# SIM7600G-H.net
KiCad netlist of a schematic drawn in Altium Designer
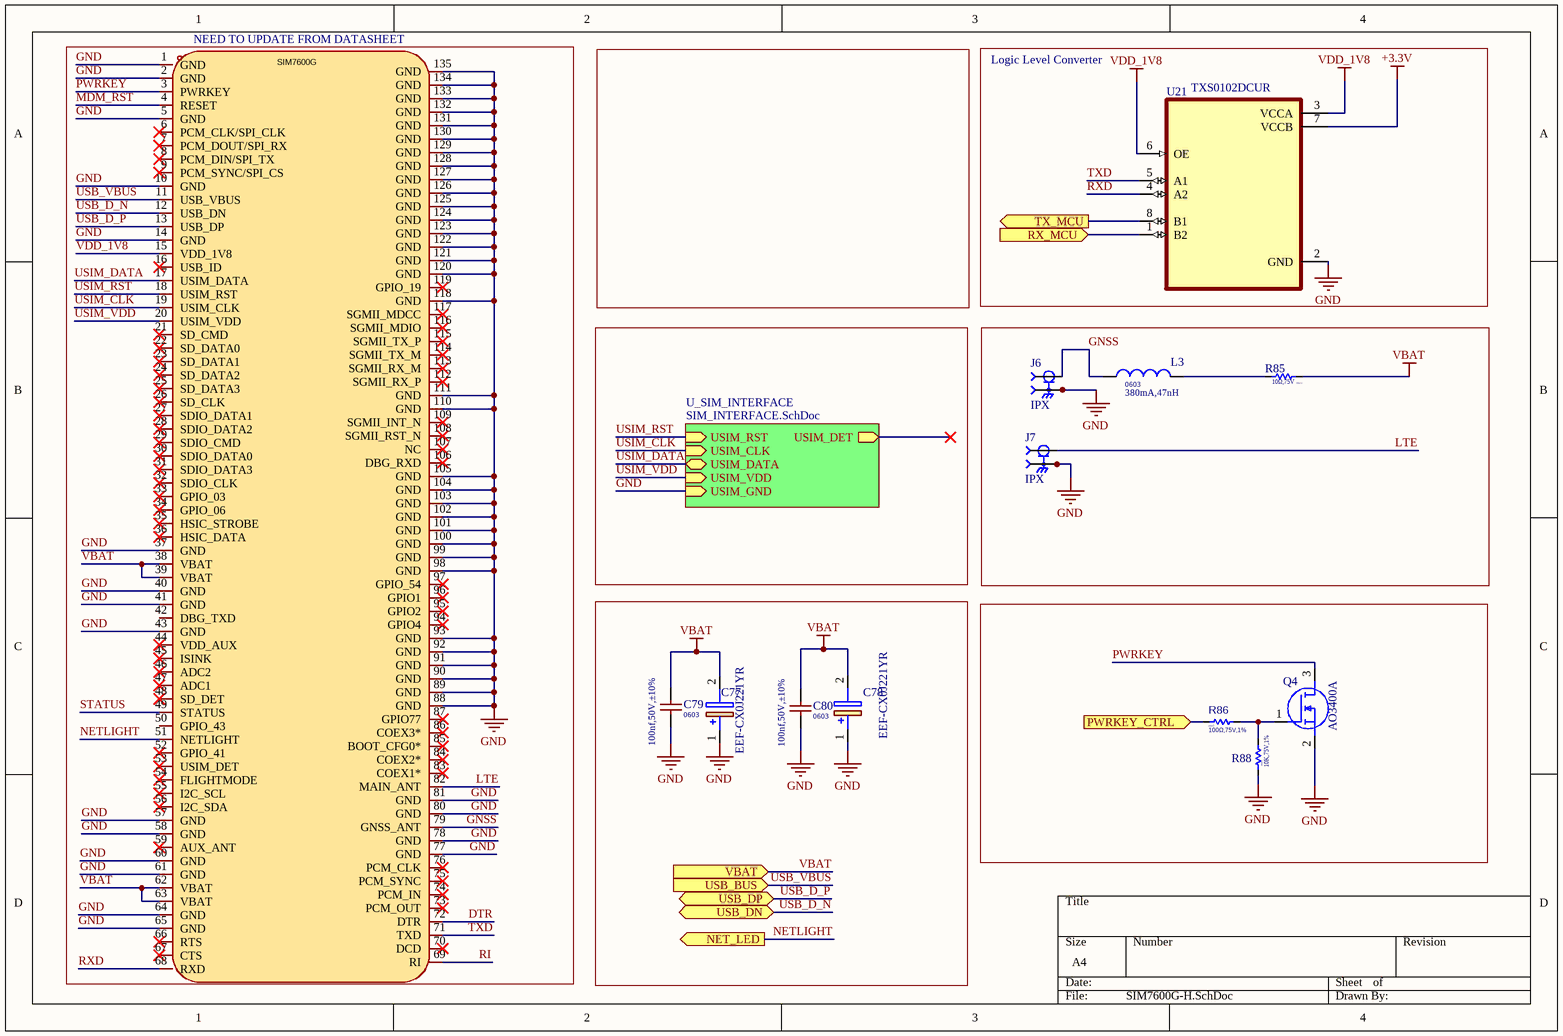
[diagram p0: SIM7600G-H.SchDoc]

(export (version "E")
  (design (tool "Eeschema 10.0.6"))
  (components
    (comp (ref "C77")
      (value "EEF-CX0J221YR")
      (footprint "CAPPM7343X200N")
      (description "Capacitor Polarised")
      (libsource (lib "RCL") (part "EEF-CX0J221YR"))
    )
    (comp (ref "C78")
      (value "EEF-CX0J221YR")
      (footprint "CAPPM7343X200N")
      (description "Capacitor Polarised")
      (libsource (lib "RCL") (part "EEF-CX0J221YR"))
    )
    (comp (ref "C79")
      (value "100nf,50V,±10%")
      (footprint "C0603")
      (description "50V 100nF X7R ±10% 0603 Multilayer Ceramic Capacitors MLCC - SMD/SMT ROHS")
      (fields
        (field (name "MPN") "603-CC603KRX7R9BB104")
        (field (name "MANUFACTURER") "KEMET")
        (field (name "PACKAGE") "0603")
      )
      (libsource (lib "RCL") (part "CC0603KRX7R9BB104"))
    )
    (comp (ref "C80")
      (value "100nf,50V,±10%")
      (footprint "C0603")
      (description "50V 100nF X7R ±10% 0603 Multilayer Ceramic Capacitors MLCC - SMD/SMT ROHS")
      (fields
        (field (name "MPN") "603-CC603KRX7R9BB104")
        (field (name "MANUFACTURER") "KEMET")
        (field (name "PACKAGE") "0603")
      )
      (libsource (lib "RCL") (part "CC0603KRX7R9BB104"))
    )
    (comp (ref "J6")
      (value "IPX")
      (footprint "connector_button:IPEX_20279-001E-03")
      (description "Small form factor with big performance through 6 GHz")
      (fields (field (name "MANUFACTURER") "I-PEX") (field (name "MPN") "20279-001E-03"))
      (libsource (lib "connector_button") (part "20279-001E-03"))
    )
    (comp (ref "J7")
      (value "IPX")
      (footprint "connector_button:IPEX_20279-001E-03")
      (description "Small form factor with big performance through 6 GHz")
      (fields (field (name "MANUFACTURER") "I-PEX") (field (name "MPN") "20279-001E-03"))
      (libsource (lib "connector_button") (part "20279-001E-03"))
    )
    (comp (ref "L3")
      (value "380mA,47nH")
      (footprint "LQW18AN47NG00D")
      (description "47 nH Unshielded Drum Core, Wirewound Inductor 380 mA 290mOhm Max 0603 (1608 Metric)")
      (fields
        (field (name "MPN") "LQW18AN47NG00D")
        (field (name "MANUFACTURER") "Murata Electronics")
        (field (name "PACKAGE") "0603")
      )
      (libsource (lib "RCL") (part "LQW18AN47NG00D"))
    )
    (comp (ref "Q4")
      (value "AO3400A")
      (footprint "SOT95P280X125-3N")
      (description "MOSFET (N-Channel)")
      (libsource (lib "MOS_TRAN") (part "AO3400A"))
    )
    (comp (ref "R85")
      (value "10Ω,75V")
      (footprint "R0603")
      (fields
        (field (name "MANUFACTURER") "Ever Ohms Tech")
        (field (name "MPN") "QR0603J10R0P05Z")
        (field (name "PACKAGE") "0603")
        (field (name "Comment") "10R")
      )
      (libsource (lib "RCL") (part "QR0603J10R0P05Z"))
    )
    (comp (ref "R86")
      (value "100Ω,75V,1%")
      (footprint "R0603")
      (description "100mW Thick Film Resistors 75V ±100ppm/℃ ±1% 100Ω 0603 Chip Resistor - Surface Mount ROHS")
      (fields
        (field (name "MANUFACTURER") "YAGEO(国巨)")
        (field (name "MPN") "AC0603FR-13100RL")
        (field (name "PACKAGE") "0603")
      )
      (libsource (lib "RCL") (part "AC0603FR-13100RL"))
    )
    (comp (ref "R88")
      (value "10K,75V,1%")
      (footprint "R0603")
      (description "100mW Thick Film Resistors ±100ppm/℃ ±1% 10kΩ 0603 Chip Resistor - Surface Mount ROHS")
      (fields
        (field (name "MPN") "0603WAF1002T5E")
        (field (name "MANUFACTURER") "UNI-ROYAL(Uniroyal Elec)")
        (field (name "PACKAGE") "0603")
      )
      (libsource (lib "RCL") (part "0603WAF1002T5E"))
    )
    (comp (ref "U21")
      (value "TXS0102DCUR")
      (footprint "IC:8-VSSOP")
      (fields (field (name "MANUFACTURER") "Texas Instruments"))
      (libsource (lib "IC") (part "TXS0102DCUR"))
    )
    (comp (ref "U22")
      (value "SIM7600G")
      (footprint "SMD,30x30mm")
      (description "SMD,30x30mm 2G/3G/4G/5G Modules ROHS")
      (fields (field (name "MANUFACTURER") "SIMCOM"))
      (libsource (lib "Module") (part "SIM7600G"))
    )
  )
  (nets
    (net (code "1") (name "+3.3V") (class "Default")
      (node (ref "U21") (pin "7") (pinfunction "VCCB_7") (pintype "power_in"))
    )
    (net (code "2") (name "/DTR") (class "Default")
      (node (ref "U22") (pin "72") (pinfunction "DTR_72") (pintype "passive"))
    )
    (net (code "3") (name "/GNSS") (class "Default")
      (node (ref "J6") (pin "1") (pinfunction "SIG_1") (pintype "passive"))
      (node (ref "L3") (pin "1") (pinfunction "1_1") (pintype "passive"))
      (node (ref "U22") (pin "79") (pinfunction "GNSS_ANT_79") (pintype "passive"))
    )
    (net (code "4") (name "/LTE") (class "Default")
      (node (ref "J7") (pin "1") (pinfunction "SIG_1") (pintype "passive"))
      (node (ref "U22") (pin "82") (pinfunction "MAIN_ANT_82") (pintype "passive"))
    )
    (net (code "5") (name "/MDM_RST") (class "Default")
      (node (ref "U22") (pin "4") (pinfunction "RESET_4") (pintype "passive"))
    )
    (net (code "6") (name "/NETLIGHT") (class "Default")
      (node (ref "U22") (pin "51") (pinfunction "NETLIGHT_51") (pintype "passive"))
    )
    (net (code "7") (name "/PWRKEY") (class "Default")
      (node (ref "Q4") (pin "3") (pinfunction "D_3") (pintype "passive"))
      (node (ref "U22") (pin "3") (pinfunction "PWRKEY_3") (pintype "passive"))
    )
    (net (code "8") (name "/PWRKEY_CTRL") (class "Default")
      (node (ref "R86") (pin "1") (pinfunction "1_1") (pintype "passive"))
    )
    (net (code "9") (name "/RI") (class "Default")
      (node (ref "U22") (pin "69") (pinfunction "RI_69") (pintype "passive"))
    )
    (net (code "10") (name "/RXD") (class "Default")
      (node (ref "U21") (pin "4") (pinfunction "A2_4") (pintype "bidirectional"))
      (node (ref "U22") (pin "68") (pinfunction "RXD_68") (pintype "passive"))
    )
    (net (code "11") (name "/RX_MCU") (class "Default")
      (node (ref "U21") (pin "1") (pinfunction "B2_1") (pintype "bidirectional"))
    )
    (net (code "12") (name "/STATUS") (class "Default")
      (node (ref "U22") (pin "49") (pinfunction "STATUS_49") (pintype "passive"))
    )
    (net (code "13") (name "/TXD") (class "Default")
      (node (ref "U21") (pin "5") (pinfunction "A1_5") (pintype "bidirectional"))
      (node (ref "U22") (pin "71") (pinfunction "TXD_71") (pintype "passive"))
    )
    (net (code "14") (name "/TX_MCU") (class "Default")
      (node (ref "U21") (pin "8") (pinfunction "B1_8") (pintype "bidirectional"))
    )
    (net (code "15") (name "/USB_D_N") (class "Default")
      (node (ref "U22") (pin "12") (pinfunction "USB_DN_12") (pintype "passive"))
    )
    (net (code "16") (name "/USB_D_P") (class "Default")
      (node (ref "U22") (pin "13") (pinfunction "USB_DP_13") (pintype "passive"))
    )
    (net (code "17") (name "/USB_VBUS") (class "Default")
      (node (ref "U22") (pin "11") (pinfunction "USB_VBUS_11") (pintype "passive"))
    )
    (net (code "18") (name "/USIM_CLK") (class "Default")
      (node (ref "U22") (pin "19") (pinfunction "USIM_CLK_19") (pintype "passive"))
    )
    (net (code "19") (name "/USIM_DATA") (class "Default")
      (node (ref "U22") (pin "17") (pinfunction "USIM_DATA_17") (pintype "passive"))
    )
    (net (code "21") (name "/USIM_RST") (class "Default")
      (node (ref "U22") (pin "18") (pinfunction "USIM_RST_18") (pintype "passive"))
    )
    (net (code "22") (name "/USIM_VDD") (class "Default")
      (node (ref "U22") (pin "20") (pinfunction "USIM_VDD_20") (pintype "passive"))
    )
    (net (code "23") (name "GND") (class "Default")
      (node (ref "C77") (pin "1") (pinfunction "+_1") (pintype "passive"))
      (node (ref "C78") (pin "1") (pinfunction "+_1") (pintype "passive"))
      (node (ref "C79") (pin "1") (pinfunction "1_1") (pintype "passive"))
      (node (ref "C80") (pin "1") (pinfunction "1_1") (pintype "passive"))
      (node (ref "J6") (pin "2") (pinfunction "GND_2") (pintype "passive"))
      (node (ref "J6") (pin "3") (pinfunction "GND_3") (pintype "passive"))
      (node (ref "J7") (pin "2") (pinfunction "GND_2") (pintype "passive"))
      (node (ref "J7") (pin "3") (pinfunction "GND_3") (pintype "passive"))
      (node (ref "Q4") (pin "2") (pinfunction "S_2") (pintype "passive"))
      (node (ref "R88") (pin "1") (pinfunction "1_1") (pintype "passive"))
      (node (ref "U21") (pin "2") (pinfunction "GND_2") (pintype "power_in"))
      (node (ref "U22") (pin "1") (pinfunction "GND_1") (pintype "passive"))
      (node (ref "U22") (pin "10") (pinfunction "GND_10") (pintype "passive"))
      (node (ref "U22") (pin "100") (pinfunction "GND_100") (pintype "passive"))
      (node (ref "U22") (pin "101") (pinfunction "GND_101") (pintype "passive"))
      (node (ref "U22") (pin "102") (pinfunction "GND_102") (pintype "passive"))
      (node (ref "U22") (pin "103") (pinfunction "GND_103") (pintype "passive"))
      (node (ref "U22") (pin "104") (pinfunction "GND_104") (pintype "passive"))
      (node (ref "U22") (pin "105") (pinfunction "GND_105") (pintype "passive"))
      (node (ref "U22") (pin "110") (pinfunction "GND_110") (pintype "passive"))
      (node (ref "U22") (pin "111") (pinfunction "GND_111") (pintype "passive"))
      (node (ref "U22") (pin "118") (pinfunction "GND_118") (pintype "passive"))
      (node (ref "U22") (pin "120") (pinfunction "GND_120") (pintype "passive"))
      (node (ref "U22") (pin "121") (pinfunction "GND_121") (pintype "passive"))
      (node (ref "U22") (pin "122") (pinfunction "GND_122") (pintype "passive"))
      (node (ref "U22") (pin "123") (pinfunction "GND_123") (pintype "passive"))
      (node (ref "U22") (pin "124") (pinfunction "GND_124") (pintype "passive"))
      (node (ref "U22") (pin "125") (pinfunction "GND_125") (pintype "passive"))
      (node (ref "U22") (pin "126") (pinfunction "GND_126") (pintype "passive"))
      (node (ref "U22") (pin "127") (pinfunction "GND_127") (pintype "passive"))
      (node (ref "U22") (pin "128") (pinfunction "GND_128") (pintype "passive"))
      (node (ref "U22") (pin "129") (pinfunction "GND_129") (pintype "passive"))
      (node (ref "U22") (pin "130") (pinfunction "GND_130") (pintype "passive"))
      (node (ref "U22") (pin "131") (pinfunction "GND_131") (pintype "passive"))
      (node (ref "U22") (pin "132") (pinfunction "GND_132") (pintype "passive"))
      (node (ref "U22") (pin "133") (pinfunction "GND_133") (pintype "passive"))
      (node (ref "U22") (pin "134") (pinfunction "GND_134") (pintype "passive"))
      (node (ref "U22") (pin "135") (pinfunction "GND_135") (pintype "passive"))
      (node (ref "U22") (pin "14") (pinfunction "GND_14") (pintype "passive"))
      (node (ref "U22") (pin "2") (pinfunction "GND_2") (pintype "passive"))
      (node (ref "U22") (pin "37") (pinfunction "GND_37") (pintype "passive"))
      (node (ref "U22") (pin "40") (pinfunction "GND_40") (pintype "passive"))
      (node (ref "U22") (pin "41") (pinfunction "GND_41") (pintype "passive"))
      (node (ref "U22") (pin "43") (pinfunction "GND_43") (pintype "passive"))
      (node (ref "U22") (pin "5") (pinfunction "GND_5") (pintype "passive"))
      (node (ref "U22") (pin "57") (pinfunction "GND_57") (pintype "passive"))
      (node (ref "U22") (pin "58") (pinfunction "GND_58") (pintype "passive"))
      (node (ref "U22") (pin "60") (pinfunction "GND_60") (pintype "passive"))
      (node (ref "U22") (pin "61") (pinfunction "GND_61") (pintype "passive"))
      (node (ref "U22") (pin "64") (pinfunction "GND_64") (pintype "passive"))
      (node (ref "U22") (pin "65") (pinfunction "GND_65") (pintype "passive"))
      (node (ref "U22") (pin "77") (pinfunction "GND_77") (pintype "passive"))
      (node (ref "U22") (pin "78") (pinfunction "GND_78") (pintype "passive"))
      (node (ref "U22") (pin "80") (pinfunction "GND_80") (pintype "passive"))
      (node (ref "U22") (pin "81") (pinfunction "GND_81") (pintype "passive"))
      (node (ref "U22") (pin "88") (pinfunction "GND_88") (pintype "passive"))
      (node (ref "U22") (pin "89") (pinfunction "GND_89") (pintype "passive"))
      (node (ref "U22") (pin "90") (pinfunction "GND_90") (pintype "passive"))
      (node (ref "U22") (pin "91") (pinfunction "GND_91") (pintype "passive"))
      (node (ref "U22") (pin "92") (pinfunction "GND_92") (pintype "passive"))
      (node (ref "U22") (pin "93") (pinfunction "GND_93") (pintype "passive"))
      (node (ref "U22") (pin "98") (pinfunction "GND_98") (pintype "passive"))
      (node (ref "U22") (pin "99") (pinfunction "GND_99") (pintype "passive"))
    )
    (net (code "24") (name "Net-(L3-Pad2)") (class "Default")
      (node (ref "L3") (pin "2") (pinfunction "2_2") (pintype "passive"))
      (node (ref "R85") (pin "1") (pinfunction "1_1") (pintype "passive"))
    )
    (net (code "25") (name "Net-(Q4-G)") (class "Default")
      (node (ref "Q4") (pin "1") (pinfunction "G_1") (pintype "passive"))
      (node (ref "R86") (pin "2") (pinfunction "2_2") (pintype "passive"))
      (node (ref "R88") (pin "2") (pinfunction "2_2") (pintype "passive"))
    )
    (net (code "26") (name "VBAT") (class "Default")
      (node (ref "C77") (pin "2") (pinfunction "-_2") (pintype "passive"))
      (node (ref "C78") (pin "2") (pinfunction "-_2") (pintype "passive"))
      (node (ref "C79") (pin "2") (pinfunction "2_2") (pintype "passive"))
      (node (ref "C80") (pin "2") (pinfunction "2_2") (pintype "passive"))
      (node (ref "R85") (pin "2") (pinfunction "2_2") (pintype "passive"))
      (node (ref "U22") (pin "38") (pinfunction "VBAT_38") (pintype "passive"))
      (node (ref "U22") (pin "39") (pinfunction "VBAT_39") (pintype "passive"))
      (node (ref "U22") (pin "62") (pinfunction "VBAT_62") (pintype "passive"))
      (node (ref "U22") (pin "63") (pinfunction "VBAT_63") (pintype "passive"))
    )
    (net (code "27") (name "VDD_1V8") (class "Default")
      (node (ref "U21") (pin "3") (pinfunction "VCCA_3") (pintype "power_in"))
      (node (ref "U21") (pin "6") (pinfunction "OE_6") (pintype "input"))
      (node (ref "U22") (pin "15") (pinfunction "VDD_1V8_15") (pintype "passive"))
    )
    (net (code "28") (name "unconnected-(U22-ADC1-Pad47)") (class "Default")
      (node (ref "U22") (pin "47") (pinfunction "ADC1_47") (pintype "passive+no_connect"))
    )
    (net (code "29") (name "unconnected-(U22-ADC2-Pad46)") (class "Default")
      (node (ref "U22") (pin "46") (pinfunction "ADC2_46") (pintype "passive+no_connect"))
    )
    (net (code "30") (name "unconnected-(U22-AUX_ANT-Pad59)") (class "Default")
      (node (ref "U22") (pin "59") (pinfunction "AUX_ANT_59") (pintype "passive+no_connect"))
    )
    (net (code "31") (name "unconnected-(U22-BOOT_CFG0*-Pad85)") (class "Default")
      (node (ref "U22") (pin "85") (pinfunction "BOOT_CFG0*_85") (pintype "passive+no_connect"))
    )
    (net (code "32") (name "unconnected-(U22-COEX1*-Pad83)") (class "Default")
      (node (ref "U22") (pin "83") (pinfunction "COEX1*_83") (pintype "passive+no_connect"))
    )
    (net (code "33") (name "unconnected-(U22-COEX2*-Pad84)") (class "Default")
      (node (ref "U22") (pin "84") (pinfunction "COEX2*_84") (pintype "passive+no_connect"))
    )
    (net (code "34") (name "unconnected-(U22-COEX3*-Pad86)") (class "Default")
      (node (ref "U22") (pin "86") (pinfunction "COEX3*_86") (pintype "passive+no_connect"))
    )
    (net (code "35") (name "unconnected-(U22-CTS-Pad67)") (class "Default")
      (node (ref "U22") (pin "67") (pinfunction "CTS_67") (pintype "passive+no_connect"))
    )
    (net (code "36") (name "unconnected-(U22-DBG_RXD-Pad106)") (class "Default")
      (node (ref "U22") (pin "106") (pinfunction "DBG_RXD_106") (pintype "passive+no_connect"))
    )
    (net (code "37") (name "unconnected-(U22-DBG_TXD-Pad42)") (class "Default")
      (node (ref "U22") (pin "42") (pinfunction "DBG_TXD_42") (pintype "passive"))
    )
    (net (code "38") (name "unconnected-(U22-DCD-Pad70)") (class "Default")
      (node (ref "U22") (pin "70") (pinfunction "DCD_70") (pintype "passive+no_connect"))
    )
    (net (code "39") (name "unconnected-(U22-FLIGHTMODE-Pad54)") (class "Default")
      (node (ref "U22") (pin "54") (pinfunction "FLIGHTMODE_54") (pintype "passive+no_connect"))
    )
    (net (code "40") (name "unconnected-(U22-GPIO1-Pad96)") (class "Default")
      (node (ref "U22") (pin "96") (pinfunction "GPIO1_96") (pintype "passive+no_connect"))
    )
    (net (code "41") (name "unconnected-(U22-GPIO2-Pad95)") (class "Default")
      (node (ref "U22") (pin "95") (pinfunction "GPIO2_95") (pintype "passive+no_connect"))
    )
    (net (code "42") (name "unconnected-(U22-GPIO4-Pad94)") (class "Default")
      (node (ref "U22") (pin "94") (pinfunction "GPIO4_94") (pintype "passive+no_connect"))
    )
    (net (code "43") (name "unconnected-(U22-GPIO77-Pad87)") (class "Default")
      (node (ref "U22") (pin "87") (pinfunction "GPIO77_87") (pintype "passive+no_connect"))
    )
    (net (code "44") (name "unconnected-(U22-GPIO_03-Pad33)") (class "Default")
      (node (ref "U22") (pin "33") (pinfunction "GPIO_03_33") (pintype "passive+no_connect"))
    )
    (net (code "45") (name "unconnected-(U22-GPIO_06-Pad34)") (class "Default")
      (node (ref "U22") (pin "34") (pinfunction "GPIO_06_34") (pintype "passive+no_connect"))
    )
    (net (code "46") (name "unconnected-(U22-GPIO_19-Pad119)") (class "Default")
      (node (ref "U22") (pin "119") (pinfunction "GPIO_19_119") (pintype "passive+no_connect"))
    )
    (net (code "47") (name "unconnected-(U22-GPIO_41-Pad52)") (class "Default")
      (node (ref "U22") (pin "52") (pinfunction "GPIO_41_52") (pintype "passive+no_connect"))
    )
    (net (code "48") (name "unconnected-(U22-GPIO_43-Pad50)") (class "Default")
      (node (ref "U22") (pin "50") (pinfunction "GPIO_43_50") (pintype "passive"))
    )
    (net (code "49") (name "unconnected-(U22-GPIO_54-Pad97)") (class "Default")
      (node (ref "U22") (pin "97") (pinfunction "GPIO_54_97") (pintype "passive+no_connect"))
    )
    (net (code "50") (name "unconnected-(U22-HSIC_DATA-Pad36)") (class "Default")
      (node (ref "U22") (pin "36") (pinfunction "HSIC_DATA_36") (pintype "passive+no_connect"))
    )
    (net (code "51") (name "unconnected-(U22-HSIC_STROBE-Pad35)") (class "Default")
      (node (ref "U22") (pin "35") (pinfunction "HSIC_STROBE_35") (pintype "passive+no_connect"))
    )
    (net (code "52") (name "unconnected-(U22-I2C_SCL-Pad55)") (class "Default")
      (node (ref "U22") (pin "55") (pinfunction "I2C_SCL_55") (pintype "passive+no_connect"))
    )
    (net (code "53") (name "unconnected-(U22-I2C_SDA-Pad56)") (class "Default")
      (node (ref "U22") (pin "56") (pinfunction "I2C_SDA_56") (pintype "passive+no_connect"))
    )
    (net (code "54") (name "unconnected-(U22-ISINK-Pad45)") (class "Default")
      (node (ref "U22") (pin "45") (pinfunction "ISINK_45") (pintype "passive+no_connect"))
    )
    (net (code "55") (name "unconnected-(U22-NC-Pad107)") (class "Default")
      (node (ref "U22") (pin "107") (pinfunction "NC_107") (pintype "passive+no_connect"))
    )
    (net (code "56") (name "unconnected-(U22-PCM_CLK-Pad76)") (class "Default")
      (node (ref "U22") (pin "76") (pinfunction "PCM_CLK_76") (pintype "passive+no_connect"))
    )
    (net (code "57") (name "unconnected-(U22-PCM_CLK{slash}SPI_CLK-Pad6)") (class "Default")
      (node (ref "U22") (pin "6") (pinfunction "PCM_CLK/SPI_CLK_6") (pintype "passive+no_connect"))
    )
    (net (code "58") (name "unconnected-(U22-PCM_DIN{slash}SPI_TX-Pad8)") (class "Default")
      (node (ref "U22") (pin "8") (pinfunction "PCM_DIN/SPI_TX_8") (pintype "passive+no_connect"))
    )
    (net (code "59") (name "unconnected-(U22-PCM_DOUT{slash}SPI_RX-Pad7)") (class "Default")
      (node (ref "U22") (pin "7") (pinfunction "PCM_DOUT/SPI_RX_7") (pintype "passive+no_connect"))
    )
    (net (code "60") (name "unconnected-(U22-PCM_IN-Pad74)") (class "Default")
      (node (ref "U22") (pin "74") (pinfunction "PCM_IN_74") (pintype "passive+no_connect"))
    )
    (net (code "61") (name "unconnected-(U22-PCM_OUT-Pad73)") (class "Default")
      (node (ref "U22") (pin "73") (pinfunction "PCM_OUT_73") (pintype "passive+no_connect"))
    )
    (net (code "62") (name "unconnected-(U22-PCM_SYNC-Pad75)") (class "Default")
      (node (ref "U22") (pin "75") (pinfunction "PCM_SYNC_75") (pintype "passive+no_connect"))
    )
    (net (code "63") (name "unconnected-(U22-PCM_SYNC{slash}SPI_CS-Pad9)") (class "Default")
      (node (ref "U22") (pin "9") (pinfunction "PCM_SYNC/SPI_CS_9") (pintype "passive+no_connect"))
    )
    (net (code "64") (name "unconnected-(U22-RTS-Pad66)") (class "Default")
      (node (ref "U22") (pin "66") (pinfunction "RTS_66") (pintype "passive+no_connect"))
    )
    (net (code "65") (name "unconnected-(U22-SDIO_CLK-Pad32)") (class "Default")
      (node (ref "U22") (pin "32") (pinfunction "SDIO_CLK_32") (pintype "passive+no_connect"))
    )
    (net (code "66") (name "unconnected-(U22-SDIO_CMD-Pad29)") (class "Default")
      (node (ref "U22") (pin "29") (pinfunction "SDIO_CMD_29") (pintype "passive+no_connect"))
    )
    (net (code "67") (name "unconnected-(U22-SDIO_DATA0-Pad30)") (class "Default")
      (node (ref "U22") (pin "30") (pinfunction "SDIO_DATA0_30") (pintype "passive+no_connect"))
    )
    (net (code "68") (name "unconnected-(U22-SDIO_DATA1-Pad27)") (class "Default")
      (node (ref "U22") (pin "27") (pinfunction "SDIO_DATA1_27") (pintype "passive+no_connect"))
    )
    (net (code "69") (name "unconnected-(U22-SDIO_DATA2-Pad28)") (class "Default")
      (node (ref "U22") (pin "28") (pinfunction "SDIO_DATA2_28") (pintype "passive+no_connect"))
    )
    (net (code "70") (name "unconnected-(U22-SDIO_DATA3-Pad31)") (class "Default")
      (node (ref "U22") (pin "31") (pinfunction "SDIO_DATA3_31") (pintype "passive+no_connect"))
    )
    (net (code "71") (name "unconnected-(U22-SD_CLK-Pad26)") (class "Default")
      (node (ref "U22") (pin "26") (pinfunction "SD_CLK_26") (pintype "passive+no_connect"))
    )
    (net (code "72") (name "unconnected-(U22-SD_CMD-Pad21)") (class "Default")
      (node (ref "U22") (pin "21") (pinfunction "SD_CMD_21") (pintype "passive+no_connect"))
    )
    (net (code "73") (name "unconnected-(U22-SD_DATA0-Pad22)") (class "Default")
      (node (ref "U22") (pin "22") (pinfunction "SD_DATA0_22") (pintype "passive+no_connect"))
    )
    (net (code "74") (name "unconnected-(U22-SD_DATA1-Pad23)") (class "Default")
      (node (ref "U22") (pin "23") (pinfunction "SD_DATA1_23") (pintype "passive+no_connect"))
    )
    (net (code "75") (name "unconnected-(U22-SD_DATA2-Pad24)") (class "Default")
      (node (ref "U22") (pin "24") (pinfunction "SD_DATA2_24") (pintype "passive+no_connect"))
    )
    (net (code "76") (name "unconnected-(U22-SD_DATA3-Pad25)") (class "Default")
      (node (ref "U22") (pin "25") (pinfunction "SD_DATA3_25") (pintype "passive+no_connect"))
    )
    (net (code "77") (name "unconnected-(U22-SD_DET-Pad48)") (class "Default")
      (node (ref "U22") (pin "48") (pinfunction "SD_DET_48") (pintype "passive+no_connect"))
    )
    (net (code "78") (name "unconnected-(U22-SGMII_INT_N-Pad109)") (class "Default")
      (node (ref "U22") (pin "109") (pinfunction "SGMII_INT_N_109") (pintype "passive+no_connect"))
    )
    (net (code "79") (name "unconnected-(U22-SGMII_MDCC-Pad117)") (class "Default")
      (node (ref "U22") (pin "117") (pinfunction "SGMII_MDCC_117") (pintype "passive+no_connect"))
    )
    (net (code "80") (name "unconnected-(U22-SGMII_MDIO-Pad116)") (class "Default")
      (node (ref "U22") (pin "116") (pinfunction "SGMII_MDIO_116") (pintype "passive+no_connect"))
    )
    (net (code "81") (name "unconnected-(U22-SGMII_RST_N-Pad108)") (class "Default")
      (node (ref "U22") (pin "108") (pinfunction "SGMII_RST_N_108") (pintype "passive+no_connect"))
    )
    (net (code "82") (name "unconnected-(U22-SGMII_RX_M-Pad113)") (class "Default")
      (node (ref "U22") (pin "113") (pinfunction "SGMII_RX_M_113") (pintype "passive+no_connect"))
    )
    (net (code "83") (name "unconnected-(U22-SGMII_RX_P-Pad112)") (class "Default")
      (node (ref "U22") (pin "112") (pinfunction "SGMII_RX_P_112") (pintype "passive+no_connect"))
    )
    (net (code "84") (name "unconnected-(U22-SGMII_TX_M-Pad114)") (class "Default")
      (node (ref "U22") (pin "114") (pinfunction "SGMII_TX_M_114") (pintype "passive+no_connect"))
    )
    (net (code "85") (name "unconnected-(U22-SGMII_TX_P-Pad115)") (class "Default")
      (node (ref "U22") (pin "115") (pinfunction "SGMII_TX_P_115") (pintype "passive+no_connect"))
    )
    (net (code "86") (name "unconnected-(U22-USB_ID-Pad16)") (class "Default")
      (node (ref "U22") (pin "16") (pinfunction "USB_ID_16") (pintype "passive+no_connect"))
    )
    (net (code "87") (name "unconnected-(U22-USIM_DET-Pad53)") (class "Default")
      (node (ref "U22") (pin "53") (pinfunction "USIM_DET_53") (pintype "passive+no_connect"))
    )
    (net (code "88") (name "unconnected-(U22-VDD_AUX-Pad44)") (class "Default")
      (node (ref "U22") (pin "44") (pinfunction "VDD_AUX_44") (pintype "passive+no_connect"))
    )
  )
)
